# BuckConverter.net
KiCad netlist of a schematic drawn in Altium Designer
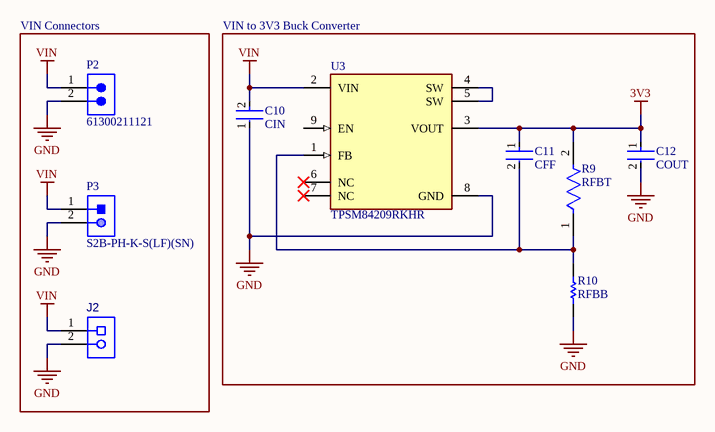
[diagram p0: BuckConverter.SchDoc]

(export (version "E")
  (design (tool "Eeschema 10.0.6"))
  (components
    (comp (ref "C10")
      (value "CIN")
      (footprint "FP-C1608-080-0_1-MFG")
      (description "Multilayer Ceramic Capacitors 2.2μF ±10% 35V X5R SMD 0603")
      (fields (field (name "TOLERANCE") "10%") (field (name "VOLTAGE") "35V"))
      (libsource (lib "Altium Content Vault") (part "236180d848d6139a670b325ea6854c9"))
    )
    (comp (ref "C11")
      (value "CFF")
      (footprint "FP-GRM033-0_03-IPC_C")
      (description "Chip Multilayer Ceramic Capacitors for General Purpose, 0201, 330pF, X7R, 15%, 10%, 25V")
      (fields (field (name "VOLTAGE") "25V") (field (name "TOLERANCE") "10%"))
      (libsource (lib "Altium Content Vault") (part "b4654b650e69147ec39a6b967a45e02"))
    )
    (comp (ref "C12")
      (value "COUT")
      (footprint "FP-C2012-125-0_2-IPC_A")
      (description "Multilayer Ceramic Capacitors 33μF ±20% 10V X5R SMD 0805")
      (fields (field (name "TOLERANCE") "20%"))
      (libsource (lib "Altium Content Vault") (part "b4654b650e69147ec39a6b967a45e02"))
    )
    (comp (ref "J2")
      (value "1729128")
      (footprint "PHOE-1729128-2_V")
      (description "PCB Terminal Block, 13.5 A, 400 V, 2-Pin THD, RoHS, Bulk")
      (fields (field (name "MANUFACTURER") "Phoenix Contact"))
      (libsource (lib "Altium Content Vault") (part "CN-2P-F-R2"))
    )
    (comp (ref "P2")
      (value "61300211121")
      (footprint "61300211121")
      (libsource (lib "Altium Content Vault") (part "Header_Male_1R_02P"))
    )
    (comp (ref "P3")
      (value "S2B-PH-K-S(LF)(SN)")
      (footprint "JST-S2B-PH-K-S_V")
      (fields (field (name "TOLERANCE") "20%"))
      (libsource (lib "Altium Content Vault") (part "CN-1P-M-R2"))
    )
    (comp (ref "R9")
      (value "RFBT")
      (footprint "FP-CRCW0402-e3-IPC_B")
      (description "RES SMD 10K OHM 1% 1/16W 0402")
      (fields (field (name "TOLERANCE") "1%"))
      (libsource (lib "Altium Content Vault") (part "1029c3af85768c4190bb7ad29bc67b5"))
    )
    (comp (ref "R10")
      (value "RFBB")
      (footprint "RESC1608X55X25LL10T15")
      (fields (field (name "TOLERANCE") "1%") (field (name "MANUFACTURER") "Yageo"))
      (libsource (lib "Altium Content Vault") (part "RES-2"))
    )
    (comp (ref "U3")
      (value "TPSM84209RKHR")
      (footprint "FP-RKH0009A-MFG")
      (description "DC DC CONVERTER 1.2-6V")
      (libsource (lib "Altium Content Vault") (part "5195406eaf4ebe97fbc3c0702d316f5"))
    )
  )
  (nets
    (net (code "1") (name "3V3") (class "Default")
      (node (ref "C11") (pin "1") (pinfunction "1_1") (pintype "passive"))
      (node (ref "C12") (pin "1") (pinfunction "1_1") (pintype "passive"))
      (node (ref "R9") (pin "2") (pinfunction "2_2") (pintype "passive"))
      (node (ref "U3") (pin "3") (pinfunction "VOUT_3") (pintype "passive"))
    )
    (net (code "2") (name "GND") (class "Default")
      (node (ref "C10") (pin "1") (pinfunction "1_1") (pintype "passive"))
      (node (ref "C12") (pin "2") (pinfunction "2_2") (pintype "passive"))
      (node (ref "J2") (pin "2") (pinfunction "2_2") (pintype "passive"))
      (node (ref "P2") (pin "2") (pinfunction "2_2") (pintype "passive"))
      (node (ref "P3") (pin "2") (pinfunction "2_2") (pintype "passive"))
      (node (ref "R10") (pin "1") (pinfunction "1_1") (pintype "passive"))
      (node (ref "U3") (pin "8") (pinfunction "GND_8") (pintype "power_in"))
    )
    (net (code "3") (name "Net-(U3-FB)") (class "Default")
      (node (ref "C11") (pin "2") (pinfunction "2_2") (pintype "passive"))
      (node (ref "R10") (pin "2") (pinfunction "2_2") (pintype "passive"))
      (node (ref "R9") (pin "1") (pinfunction "1_1") (pintype "passive"))
      (node (ref "U3") (pin "1") (pinfunction "FB_1") (pintype "input"))
    )
    (net (code "4") (name "Net-(U3-SW-Pad4)") (class "Default")
      (node (ref "U3") (pin "4") (pinfunction "SW_4") (pintype "power_in"))
      (node (ref "U3") (pin "5") (pinfunction "SW_5") (pintype "power_in"))
    )
    (net (code "5") (name "VIN") (class "Default")
      (node (ref "C10") (pin "2") (pinfunction "2_2") (pintype "passive"))
      (node (ref "J2") (pin "1") (pinfunction "1_1") (pintype "passive"))
      (node (ref "P2") (pin "1") (pinfunction "1_1") (pintype "passive"))
      (node (ref "P3") (pin "1") (pinfunction "1_1") (pintype "passive"))
      (node (ref "U3") (pin "2") (pinfunction "VIN_2") (pintype "power_in"))
    )
    (net (code "6") (name "unconnected-(U3-EN-Pad9)") (class "Default")
      (node (ref "U3") (pin "9") (pinfunction "EN_9") (pintype "input"))
    )
    (net (code "7") (name "unconnected-(U3-NC-Pad6)") (class "Default")
      (node (ref "U3") (pin "6") (pinfunction "NC_6") (pintype "passive+no_connect"))
    )
    (net (code "8") (name "unconnected-(U3-NC-Pad7)") (class "Default")
      (node (ref "U3") (pin "7") (pinfunction "NC_7") (pintype "passive+no_connect"))
    )
  )
)
